# PCB_Master_Traffic_Light.net
KiCad netlist of a schematic drawn in Altium Designer
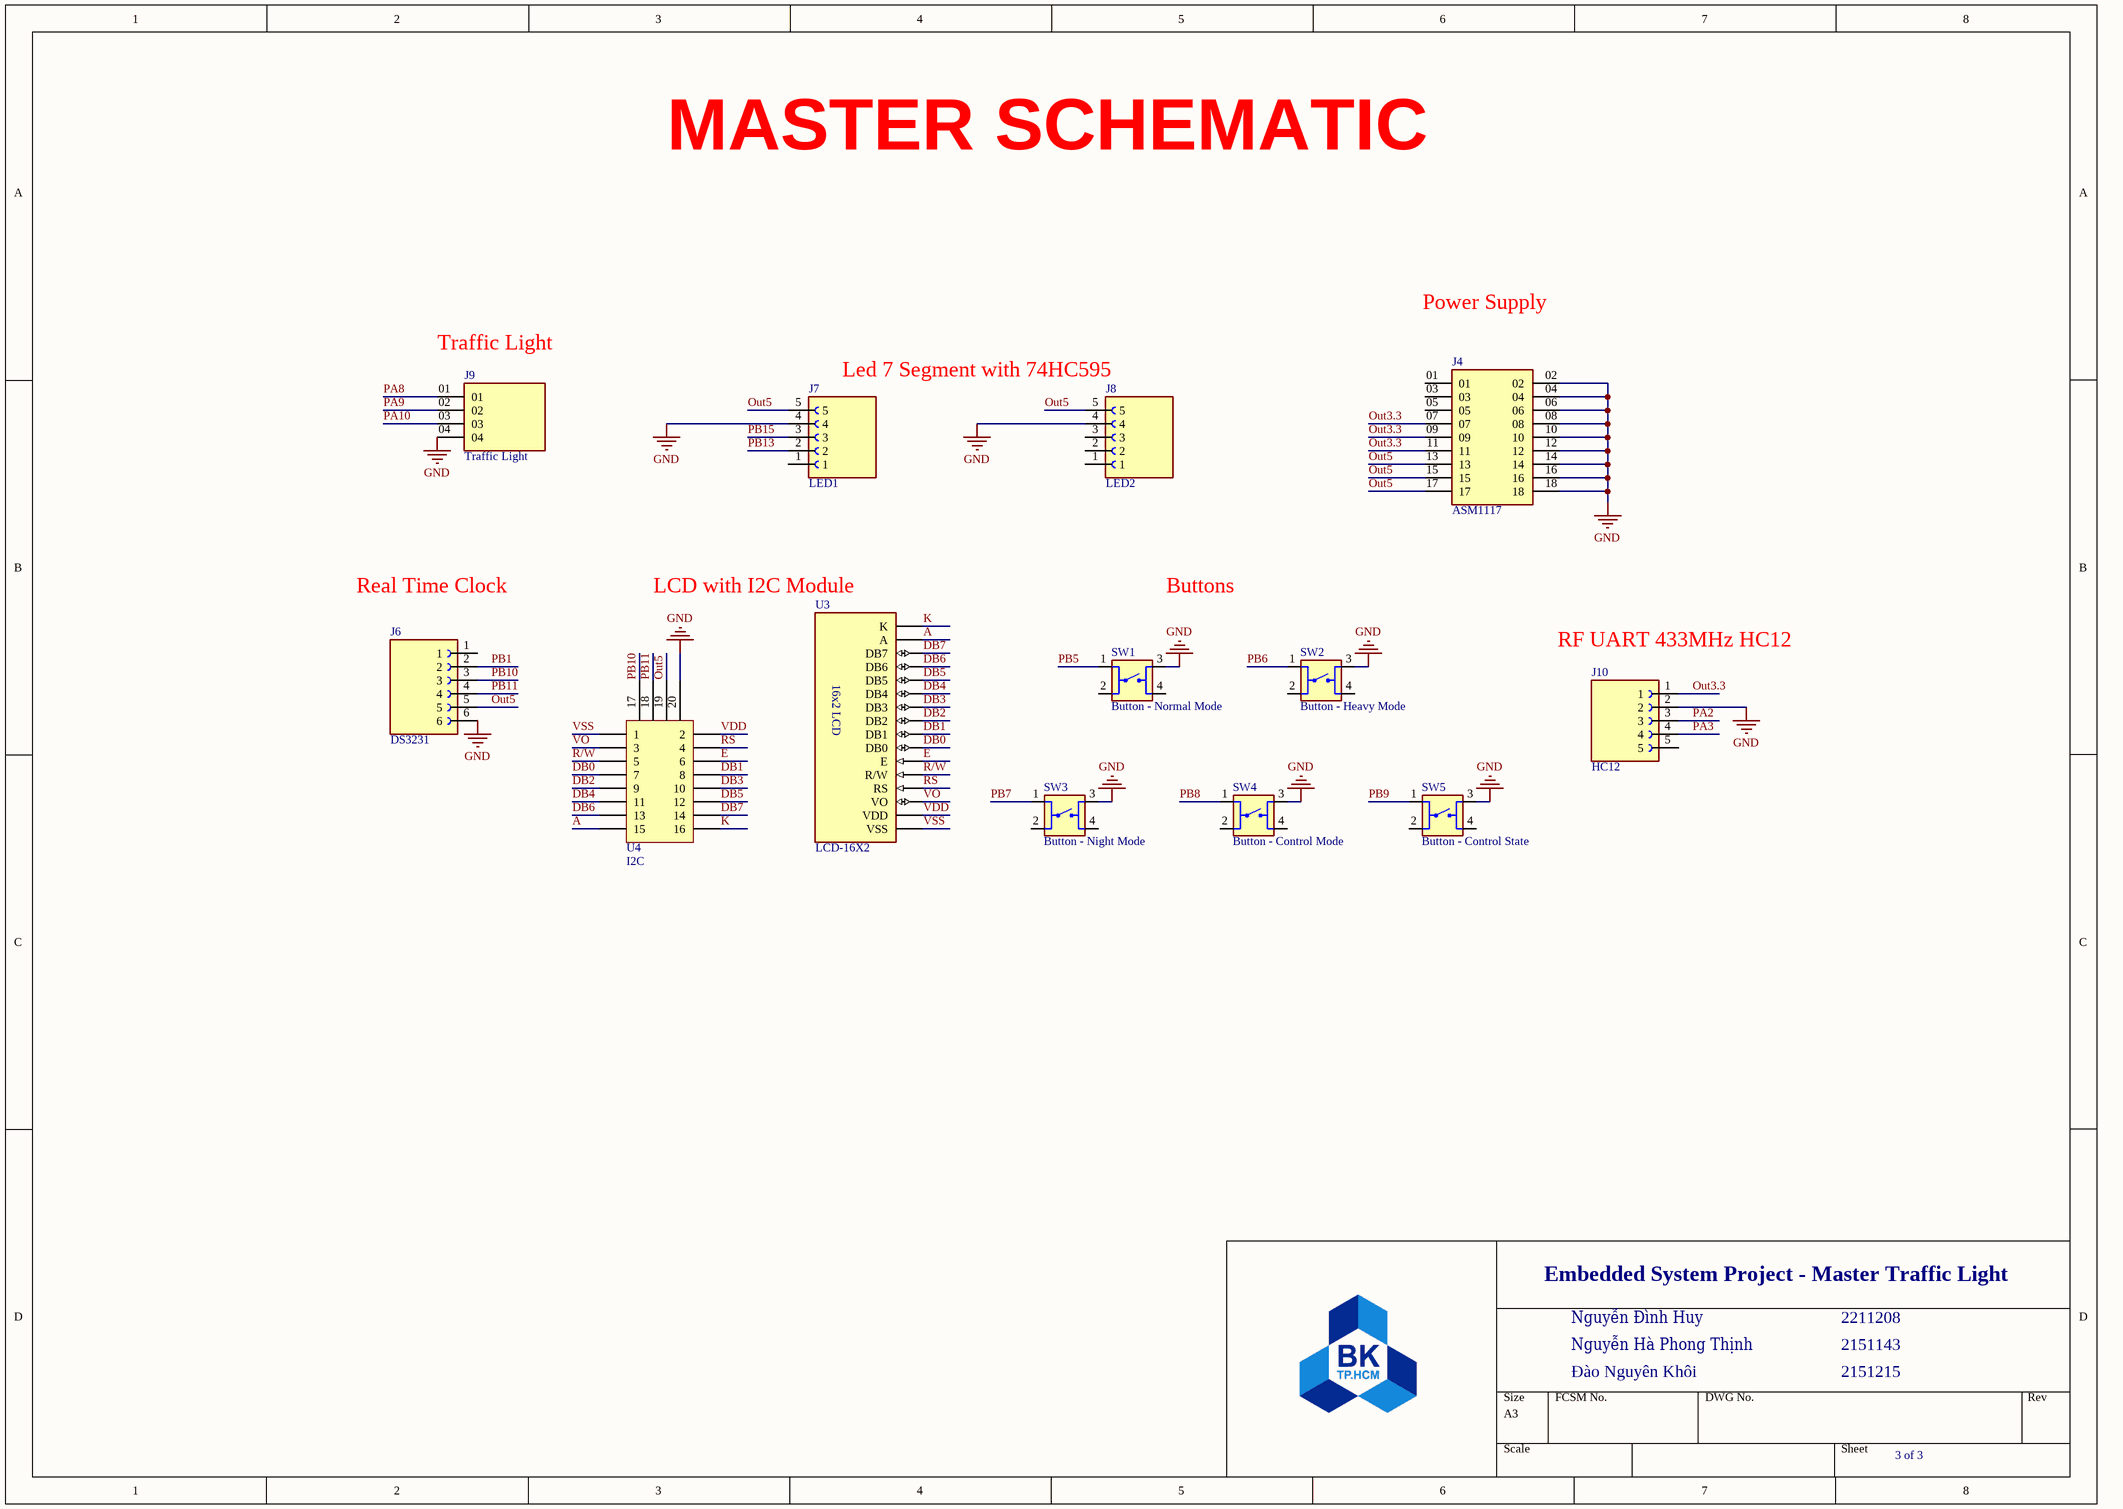
[diagram p0: PCB_Master_Traffic_Light.SchDoc]

(export (version "E")
  (design (tool "Eeschema 10.0.6"))
  (components
    (comp (ref "J4")
      (value "ASM1117")
      (footprint "SAMTEC_MTSW-109-13-G-D-905")
      (fields (field (name "MP") "MTSW-109-13-G-D-905"))
      (libsource (lib "Header 9x2") (part "MTSW-109-13-G-D-905"))
    )
    (comp (ref "J6")
      (value "DS3231")
      (footprint "HARWIN_M20-7820646")
      (fields (field (name "MP") "M20-7820646"))
      (libsource (lib "Header 6x1") (part "M20-7820646"))
    )
    (comp (ref "J7")
      (value "LED1")
      (footprint "HARWIN_M20-7820546")
      (fields (field (name "MP") "M20-7820546"))
      (libsource (lib "") (part "M20-7820546_1"))
    )
    (comp (ref "J8")
      (value "LED2")
      (footprint "HARWIN_M20-7820546")
      (fields (field (name "MP") "M20-7820546"))
      (libsource (lib "") (part "M20-7820546_1"))
    )
    (comp (ref "J9")
      (value "Traffic Light")
      (footprint "SAMTEC_HTSW-104-23-SM-S")
      (fields (field (name "MF") "Samtec") (field (name "MP") "HTSW10423SMS"))
      (libsource (lib "Header 4x1") (part "HTSW-104-23-SM-S"))
    )
    (comp (ref "J10")
      (value "HC12")
      (footprint "HARWIN_M20-7820546")
      (fields (field (name "MP") "M20-7820546"))
      (libsource (lib "Header 5x1") (part "M20-7820546"))
    )
    (comp (ref "SW1")
      (value "Button - Normal Mode")
      (footprint "SW_FSM8JH")
      (description "Tactile Switch SPST-NO Top Actuated Through Hole")
      (fields (field (name "MP") "FSM8JH") (field (name "MF") "TE Connectivity"))
      (libsource (lib "Button1") (part "FSM8JH"))
    )
    (comp (ref "SW2")
      (value "Button - Heavy Mode")
      (footprint "SW_FSM8JH")
      (description "Tactile Switch SPST-NO Top Actuated Through Hole")
      (fields (field (name "MP") "FSM8JH") (field (name "MF") "TE Connectivity"))
      (libsource (lib "Button1") (part "FSM8JH"))
    )
    (comp (ref "SW3")
      (value "Button - Night Mode")
      (footprint "SW_FSM8JH")
      (description "Tactile Switch SPST-NO Top Actuated Through Hole")
      (fields (field (name "MP") "FSM8JH") (field (name "MF") "TE Connectivity"))
      (libsource (lib "Button1") (part "FSM8JH"))
    )
    (comp (ref "SW4")
      (value "Button - Control Mode")
      (footprint "SW_FSM8JH")
      (description "Tactile Switch SPST-NO Top Actuated Through Hole")
      (fields (field (name "MP") "FSM8JH") (field (name "MF") "TE Connectivity"))
      (libsource (lib "Button1") (part "FSM8JH"))
    )
    (comp (ref "SW5")
      (value "Button - Control State")
      (footprint "SW_FSM8JH")
      (description "Tactile Switch SPST-NO Top Actuated Through Hole")
      (fields (field (name "MP") "FSM8JH") (field (name "MF") "TE Connectivity"))
      (libsource (lib "Button1") (part "FSM8JH"))
    )
    (comp (ref "U3")
      (value "LCD-16X2")
      (footprint "MODULE_LCD-16X2")
      (description "Display Development Tools 16x2 Black on Green Char LCD w Backlight")
      (fields (field (name "MF") "Gravitech"))
      (libsource (lib "LCD-16X2") (part "LCD-16X2"))
    )
    (comp (ref "U4") (value "I2C") (footprint "PCF8574") (libsource (lib "PCF8574") (part "PCF8574")))
  )
  (nets
    (net (code "1") (name "/A") (class "Default")
      (node (ref "U3") (pin "15") (pinfunction "A_15") (pintype "power_in"))
      (node (ref "U4") (pin "15") (pinfunction "15_15") (pintype "passive"))
    )
    (net (code "2") (name "/DB0") (class "Default")
      (node (ref "U3") (pin "7") (pinfunction "DB0_7") (pintype "bidirectional"))
      (node (ref "U4") (pin "7") (pinfunction "7_7") (pintype "passive"))
    )
    (net (code "3") (name "/DB1") (class "Default")
      (node (ref "U3") (pin "8") (pinfunction "DB1_8") (pintype "bidirectional"))
      (node (ref "U4") (pin "8") (pinfunction "8_8") (pintype "passive"))
    )
    (net (code "4") (name "/DB2") (class "Default")
      (node (ref "U3") (pin "9") (pinfunction "DB2_9") (pintype "bidirectional"))
      (node (ref "U4") (pin "9") (pinfunction "9_9") (pintype "passive"))
    )
    (net (code "5") (name "/DB3") (class "Default")
      (node (ref "U3") (pin "10") (pinfunction "DB3_10") (pintype "bidirectional"))
      (node (ref "U4") (pin "10") (pinfunction "10_10") (pintype "passive"))
    )
    (net (code "6") (name "/DB4") (class "Default")
      (node (ref "U3") (pin "11") (pinfunction "DB4_11") (pintype "bidirectional"))
      (node (ref "U4") (pin "11") (pinfunction "11_11") (pintype "passive"))
    )
    (net (code "7") (name "/DB5") (class "Default")
      (node (ref "U3") (pin "12") (pinfunction "DB5_12") (pintype "bidirectional"))
      (node (ref "U4") (pin "12") (pinfunction "12_12") (pintype "passive"))
    )
    (net (code "8") (name "/DB6") (class "Default")
      (node (ref "U3") (pin "13") (pinfunction "DB6_13") (pintype "bidirectional"))
      (node (ref "U4") (pin "13") (pinfunction "13_13") (pintype "passive"))
    )
    (net (code "9") (name "/DB7") (class "Default")
      (node (ref "U3") (pin "14") (pinfunction "DB7_14") (pintype "bidirectional"))
      (node (ref "U4") (pin "14") (pinfunction "14_14") (pintype "passive"))
    )
    (net (code "10") (name "/E") (class "Default")
      (node (ref "U3") (pin "6") (pinfunction "E_6") (pintype "input"))
      (node (ref "U4") (pin "6") (pinfunction "6_6") (pintype "passive"))
    )
    (net (code "11") (name "/K") (class "Default")
      (node (ref "U3") (pin "16") (pinfunction "K_16") (pintype "power_in"))
      (node (ref "U4") (pin "16") (pinfunction "16_16") (pintype "passive"))
    )
    (net (code "12") (name "/Out3.3") (class "Default")
      (node (ref "J10") (pin "1") (pinfunction "1_1") (pintype "passive"))
      (node (ref "J4") (pin "07") (pinfunction "07_07") (pintype "passive"))
      (node (ref "J4") (pin "09") (pinfunction "09_09") (pintype "passive"))
      (node (ref "J4") (pin "11") (pinfunction "11_11") (pintype "passive"))
    )
    (net (code "13") (name "/Out5") (class "Default")
      (node (ref "J4") (pin "13") (pinfunction "13_13") (pintype "passive"))
      (node (ref "J4") (pin "15") (pinfunction "15_15") (pintype "passive"))
      (node (ref "J4") (pin "17") (pinfunction "17_17") (pintype "passive"))
      (node (ref "J6") (pin "5") (pinfunction "5_5") (pintype "passive"))
      (node (ref "J7") (pin "5") (pinfunction "5_5") (pintype "passive"))
      (node (ref "J8") (pin "5") (pinfunction "5_5") (pintype "passive"))
      (node (ref "U4") (pin "19") (pinfunction "19_19") (pintype "passive"))
    )
    (net (code "14") (name "/PA2") (class "Default")
      (node (ref "J10") (pin "3") (pinfunction "3_3") (pintype "passive"))
    )
    (net (code "15") (name "/PA3") (class "Default")
      (node (ref "J10") (pin "4") (pinfunction "4_4") (pintype "passive"))
    )
    (net (code "16") (name "/PA8") (class "Default")
      (node (ref "J9") (pin "01") (pinfunction "01_01") (pintype "passive"))
    )
    (net (code "17") (name "/PA9") (class "Default")
      (node (ref "J9") (pin "02") (pinfunction "02_02") (pintype "passive"))
    )
    (net (code "18") (name "/PA10") (class "Default")
      (node (ref "J9") (pin "03") (pinfunction "03_03") (pintype "passive"))
    )
    (net (code "19") (name "/PB1") (class "Default")
      (node (ref "J6") (pin "2") (pinfunction "2_2") (pintype "passive"))
    )
    (net (code "20") (name "/PB5") (class "Default")
      (node (ref "SW1") (pin "1") (pinfunction "1_1") (pintype "passive"))
    )
    (net (code "21") (name "/PB6") (class "Default")
      (node (ref "SW2") (pin "1") (pinfunction "1_1") (pintype "passive"))
    )
    (net (code "22") (name "/PB7") (class "Default")
      (node (ref "SW3") (pin "1") (pinfunction "1_1") (pintype "passive"))
    )
    (net (code "23") (name "/PB8") (class "Default")
      (node (ref "SW4") (pin "1") (pinfunction "1_1") (pintype "passive"))
    )
    (net (code "24") (name "/PB9") (class "Default")
      (node (ref "SW5") (pin "1") (pinfunction "1_1") (pintype "passive"))
    )
    (net (code "25") (name "/PB10") (class "Default")
      (node (ref "J6") (pin "3") (pinfunction "3_3") (pintype "passive"))
      (node (ref "U4") (pin "17") (pinfunction "17_17") (pintype "passive"))
    )
    (net (code "26") (name "/PB11") (class "Default")
      (node (ref "J6") (pin "4") (pinfunction "4_4") (pintype "passive"))
      (node (ref "U4") (pin "18") (pinfunction "18_18") (pintype "passive"))
    )
    (net (code "27") (name "/PB13") (class "Default")
      (node (ref "J7") (pin "2") (pinfunction "2_2") (pintype "passive"))
    )
    (net (code "28") (name "/PB15") (class "Default")
      (node (ref "J7") (pin "3") (pinfunction "3_3") (pintype "passive"))
    )
    (net (code "29") (name "/RS") (class "Default")
      (node (ref "U3") (pin "4") (pinfunction "RS_4") (pintype "input"))
      (node (ref "U4") (pin "4") (pinfunction "4_4") (pintype "passive"))
    )
    (net (code "30") (name "/R{slash}W") (class "Default")
      (node (ref "U3") (pin "5") (pinfunction "R/W_5") (pintype "input"))
      (node (ref "U4") (pin "5") (pinfunction "5_5") (pintype "passive"))
    )
    (net (code "31") (name "/VDD") (class "Default")
      (node (ref "U3") (pin "2") (pinfunction "VDD_2") (pintype "power_in"))
      (node (ref "U4") (pin "2") (pinfunction "2_2") (pintype "passive"))
    )
    (net (code "32") (name "/VO") (class "Default")
      (node (ref "U3") (pin "3") (pinfunction "VO_3") (pintype "bidirectional"))
      (node (ref "U4") (pin "3") (pinfunction "3_3") (pintype "passive"))
    )
    (net (code "33") (name "/VSS") (class "Default")
      (node (ref "U3") (pin "1") (pinfunction "VSS_1") (pintype "power_in"))
      (node (ref "U4") (pin "1") (pinfunction "1_1") (pintype "passive"))
    )
    (net (code "34") (name "GND") (class "Default")
      (node (ref "J10") (pin "2") (pinfunction "2_2") (pintype "passive"))
      (node (ref "J4") (pin "02") (pinfunction "02_02") (pintype "passive"))
      (node (ref "J4") (pin "04") (pinfunction "04_04") (pintype "passive"))
      (node (ref "J4") (pin "06") (pinfunction "06_06") (pintype "passive"))
      (node (ref "J4") (pin "08") (pinfunction "08_08") (pintype "passive"))
      (node (ref "J4") (pin "10") (pinfunction "10_10") (pintype "passive"))
      (node (ref "J4") (pin "12") (pinfunction "12_12") (pintype "passive"))
      (node (ref "J4") (pin "14") (pinfunction "14_14") (pintype "passive"))
      (node (ref "J4") (pin "16") (pinfunction "16_16") (pintype "passive"))
      (node (ref "J4") (pin "18") (pinfunction "18_18") (pintype "passive"))
      (node (ref "J6") (pin "6") (pinfunction "6_6") (pintype "passive"))
      (node (ref "J7") (pin "4") (pinfunction "4_4") (pintype "passive"))
      (node (ref "J8") (pin "4") (pinfunction "4_4") (pintype "passive"))
      (node (ref "J9") (pin "04") (pinfunction "04_04") (pintype "passive"))
      (node (ref "SW1") (pin "3") (pinfunction "3_3") (pintype "passive"))
      (node (ref "SW2") (pin "3") (pinfunction "3_3") (pintype "passive"))
      (node (ref "SW3") (pin "3") (pinfunction "3_3") (pintype "passive"))
      (node (ref "SW4") (pin "3") (pinfunction "3_3") (pintype "passive"))
      (node (ref "SW5") (pin "3") (pinfunction "3_3") (pintype "passive"))
      (node (ref "U4") (pin "20") (pinfunction "20_20") (pintype "passive"))
    )
    (net (code "35") (name "unconnected-(J4-Pad01)") (class "Default")
      (node (ref "J4") (pin "01") (pinfunction "01_01") (pintype "passive"))
    )
    (net (code "36") (name "unconnected-(J4-Pad03)") (class "Default")
      (node (ref "J4") (pin "03") (pinfunction "03_03") (pintype "passive"))
    )
    (net (code "37") (name "unconnected-(J4-Pad05)") (class "Default")
      (node (ref "J4") (pin "05") (pinfunction "05_05") (pintype "passive"))
    )
    (net (code "38") (name "unconnected-(J6-Pad1)") (class "Default")
      (node (ref "J6") (pin "1") (pinfunction "1_1") (pintype "passive"))
    )
    (net (code "39") (name "unconnected-(J7-Pad1)") (class "Default")
      (node (ref "J7") (pin "1") (pinfunction "1_1") (pintype "passive"))
    )
    (net (code "40") (name "unconnected-(J8-Pad1)") (class "Default")
      (node (ref "J8") (pin "1") (pinfunction "1_1") (pintype "passive"))
    )
    (net (code "41") (name "unconnected-(J8-Pad2)") (class "Default")
      (node (ref "J8") (pin "2") (pinfunction "2_2") (pintype "passive"))
    )
    (net (code "42") (name "unconnected-(J8-Pad3)") (class "Default")
      (node (ref "J8") (pin "3") (pinfunction "3_3") (pintype "passive"))
    )
    (net (code "43") (name "unconnected-(J10-Pad5)") (class "Default")
      (node (ref "J10") (pin "5") (pinfunction "5_5") (pintype "passive"))
    )
    (net (code "44") (name "unconnected-(SW1-Pad2)") (class "Default")
      (node (ref "SW1") (pin "2") (pinfunction "2_2") (pintype "passive"))
    )
    (net (code "45") (name "unconnected-(SW1-Pad4)") (class "Default")
      (node (ref "SW1") (pin "4") (pinfunction "4_4") (pintype "passive"))
    )
    (net (code "46") (name "unconnected-(SW2-Pad2)") (class "Default")
      (node (ref "SW2") (pin "2") (pinfunction "2_2") (pintype "passive"))
    )
    (net (code "47") (name "unconnected-(SW2-Pad4)") (class "Default")
      (node (ref "SW2") (pin "4") (pinfunction "4_4") (pintype "passive"))
    )
    (net (code "48") (name "unconnected-(SW3-Pad2)") (class "Default")
      (node (ref "SW3") (pin "2") (pinfunction "2_2") (pintype "passive"))
    )
    (net (code "49") (name "unconnected-(SW3-Pad4)") (class "Default")
      (node (ref "SW3") (pin "4") (pinfunction "4_4") (pintype "passive"))
    )
    (net (code "50") (name "unconnected-(SW4-Pad2)") (class "Default")
      (node (ref "SW4") (pin "2") (pinfunction "2_2") (pintype "passive"))
    )
    (net (code "51") (name "unconnected-(SW4-Pad4)") (class "Default")
      (node (ref "SW4") (pin "4") (pinfunction "4_4") (pintype "passive"))
    )
    (net (code "52") (name "unconnected-(SW5-Pad2)") (class "Default")
      (node (ref "SW5") (pin "2") (pinfunction "2_2") (pintype "passive"))
    )
    (net (code "53") (name "unconnected-(SW5-Pad4)") (class "Default")
      (node (ref "SW5") (pin "4") (pinfunction "4_4") (pintype "passive"))
    )
  )
)
